# Danfoss302Pi_Interface.net
KiCad netlist of a schematic drawn in Altium Designer
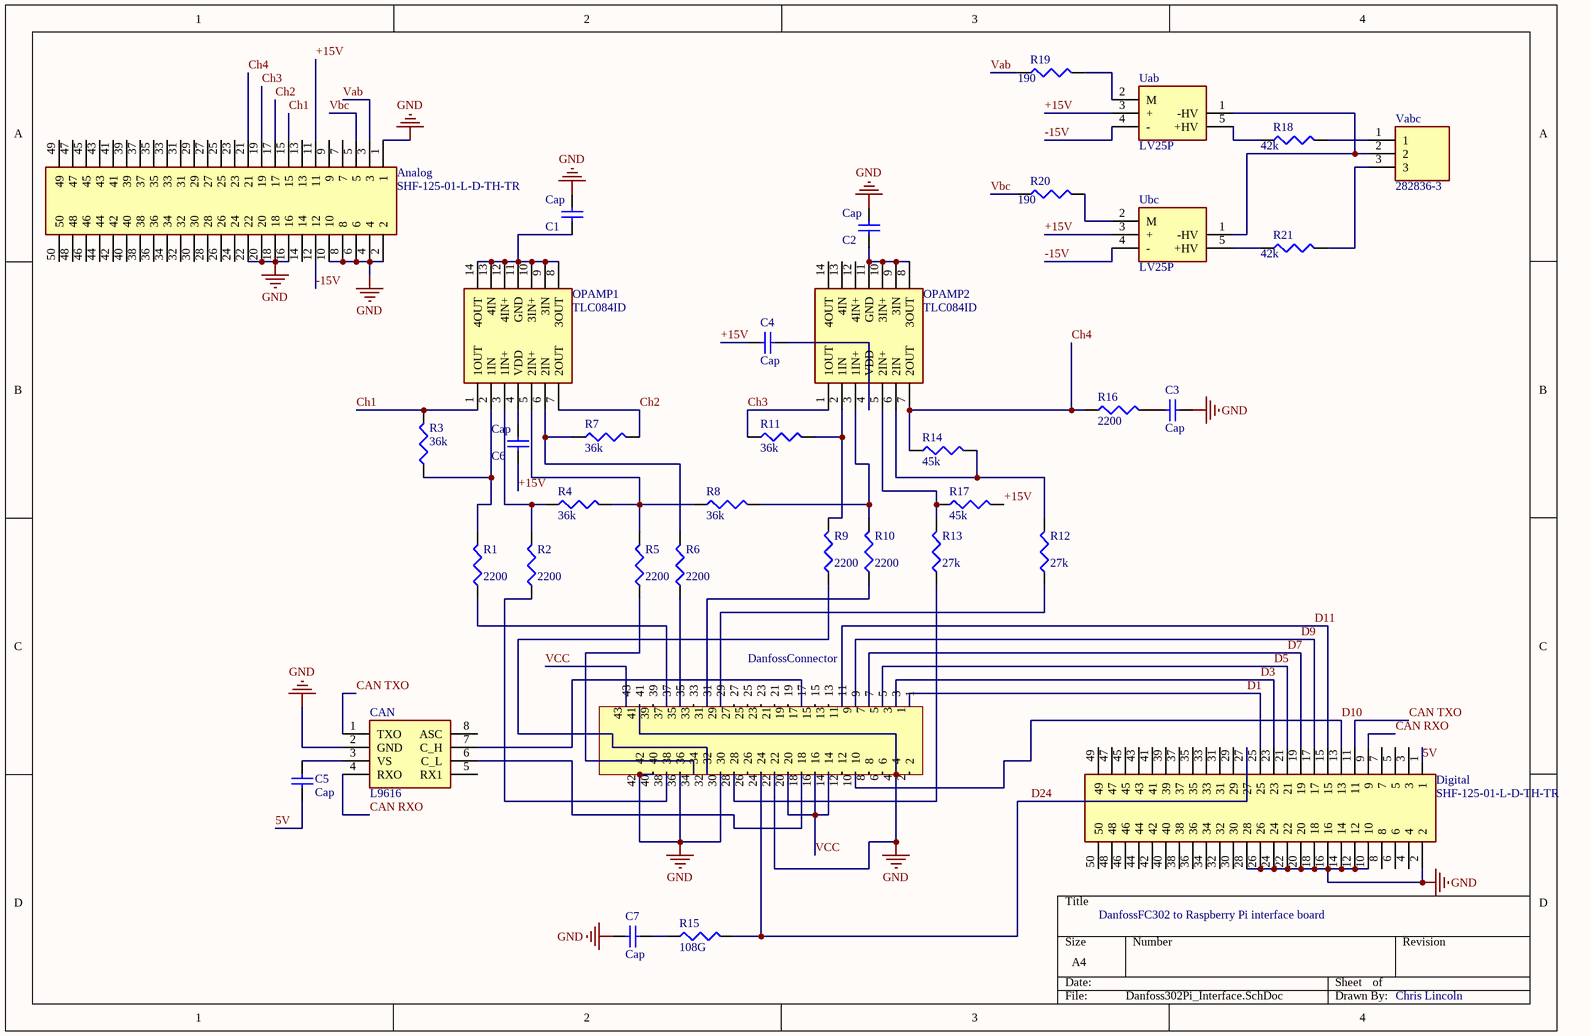
[diagram p0: Danfoss302Pi_Interface.SchDoc]

(export (version "E")
  (design (tool "Eeschema 10.0.6"))
  (components
    (comp (ref "Analog")
      (value "SHF-125-01-L-D-TH-TR")
      (footprint "SamacSys:SHF12501LDTHTR")
      (description "Connector")
      (fields (field (name "MOUSER PART NUMBER") "200-SHF12501LDTHTR"))
      (libsource (lib "*") (part "SHF-125-01-L-D-TH-TR"))
    )
    (comp (ref "C1")
      (value "Cap")
      (footprint "C1206")
      (description "Capacitor (Semiconductor SIM Model)")
      (fields (field (name "PUBLISHER") "Altium Limited"))
      (libsource (lib "Miscellaneous Devices") (part "Cap Semi"))
    )
    (comp (ref "C2")
      (value "Cap")
      (footprint "C1206")
      (description "Capacitor (Semiconductor SIM Model)")
      (fields (field (name "PUBLISHER") "Altium Limited"))
      (libsource (lib "Miscellaneous Devices") (part "Cap Semi"))
    )
    (comp (ref "C3")
      (value "Cap")
      (footprint "C1206")
      (description "Capacitor (Semiconductor SIM Model)")
      (fields (field (name "PUBLISHER") "Altium Limited"))
      (libsource (lib "Miscellaneous Devices") (part "Cap Semi"))
    )
    (comp (ref "C4")
      (value "Cap")
      (footprint "C1206")
      (description "Capacitor (Semiconductor SIM Model)")
      (fields (field (name "PUBLISHER") "Altium Limited"))
      (libsource (lib "Miscellaneous Devices") (part "Cap Semi"))
    )
    (comp (ref "C5")
      (value "Cap")
      (footprint "C1206")
      (description "Capacitor (Semiconductor SIM Model)")
      (fields (field (name "PUBLISHER") "Altium Limited"))
      (libsource (lib "Miscellaneous Devices") (part "Cap Semi"))
    )
    (comp (ref "C6")
      (value "Cap")
      (footprint "C1206")
      (description "Capacitor (Semiconductor SIM Model)")
      (fields (field (name "PUBLISHER") "Altium Limited"))
      (libsource (lib "Miscellaneous Devices") (part "Cap Semi"))
    )
    (comp (ref "C7")
      (value "Cap")
      (footprint "C1206")
      (description "Capacitor (Semiconductor SIM Model)")
      (fields (field (name "PUBLISHER") "Altium Limited"))
      (libsource (lib "Miscellaneous Devices") (part "Cap Semi"))
    )
    (comp (ref "CAN")
      (value "L9616")
      (footprint "SamacSys:SOIC127P600X175-8N")
      (description "Integrated Circuit")
      (fields (field (name "MOUSER PART NUMBER") "511-L9616"))
      (libsource (lib "*") (part "L9616"))
    )
    (comp (ref "DanfossConeector")
      (value "DanfossConnector")
      (footprint "DanfossConnector")
      (libsource (lib "Schlib1") (part "DanfossConnector"))
    )
    (comp (ref "Digital")
      (value "SHF-125-01-L-D-TH-TR")
      (footprint "SamacSys:SHF12501LDTHTR")
      (description "Connector")
      (fields (field (name "MOUSER PART NUMBER") "200-SHF12501LDTHTR"))
      (libsource (lib "*") (part "SHF-125-01-L-D-TH-TR"))
    )
    (comp (ref "OPAMP1")
      (value "TLC084ID")
      (footprint "SamacSys:SOIC127P600X175-14N")
      (description "Integrated Circuit")
      (fields (field (name "MOUSER PART NUMBER") "595-TLC084ID"))
      (libsource (lib "*") (part "TLC084ID"))
    )
    (comp (ref "OPAMP2")
      (value "TLC084ID")
      (footprint "SamacSys:SOIC127P600X175-14N")
      (description "Integrated Circuit")
      (fields (field (name "MOUSER PART NUMBER") "595-TLC084ID"))
      (libsource (lib "*") (part "TLC084ID"))
    )
    (comp (ref "R1")
      (value "2200")
      (footprint "J1-0603")
      (description "Resistor")
      (fields (field (name "Comment") "Res3") (field (name "PUBLISHER") "Altium Limited"))
      (libsource (lib "Miscellaneous Devices") (part "Res3"))
    )
    (comp (ref "R2")
      (value "2200")
      (footprint "J1-0603")
      (description "Resistor")
      (fields (field (name "Comment") "Res3") (field (name "PUBLISHER") "Altium Limited"))
      (libsource (lib "Miscellaneous Devices") (part "Res3"))
    )
    (comp (ref "R3")
      (value "36k")
      (footprint "J1-0603")
      (description "Resistor")
      (fields (field (name "Comment") "Res3") (field (name "PUBLISHER") "Altium Limited"))
      (libsource (lib "Miscellaneous Devices") (part "Res3"))
    )
    (comp (ref "R4")
      (value "36k")
      (footprint "J1-0603")
      (description "Resistor")
      (fields (field (name "Comment") "Res3") (field (name "PUBLISHER") "Altium Limited"))
      (libsource (lib "Miscellaneous Devices") (part "Res3"))
    )
    (comp (ref "R5")
      (value "2200")
      (footprint "J1-0603")
      (description "Resistor")
      (fields (field (name "Comment") "Res3") (field (name "PUBLISHER") "Altium Limited"))
      (libsource (lib "Miscellaneous Devices") (part "Res3"))
    )
    (comp (ref "R6")
      (value "2200")
      (footprint "J1-0603")
      (description "Resistor")
      (fields (field (name "Comment") "Res3") (field (name "PUBLISHER") "Altium Limited"))
      (libsource (lib "Miscellaneous Devices") (part "Res3"))
    )
    (comp (ref "R7")
      (value "36k")
      (footprint "J1-0603")
      (description "Resistor")
      (fields (field (name "Comment") "Res3") (field (name "PUBLISHER") "Altium Limited"))
      (libsource (lib "Miscellaneous Devices") (part "Res3"))
    )
    (comp (ref "R8")
      (value "36k")
      (footprint "J1-0603")
      (description "Resistor")
      (fields (field (name "Comment") "Res3") (field (name "PUBLISHER") "Altium Limited"))
      (libsource (lib "Miscellaneous Devices") (part "Res3"))
    )
    (comp (ref "R9")
      (value "2200")
      (footprint "J1-0603")
      (description "Resistor")
      (fields (field (name "Comment") "Res3") (field (name "PUBLISHER") "Altium Limited"))
      (libsource (lib "Miscellaneous Devices") (part "Res3"))
    )
    (comp (ref "R10")
      (value "2200")
      (footprint "J1-0603")
      (description "Resistor")
      (fields (field (name "Comment") "Res3") (field (name "PUBLISHER") "Altium Limited"))
      (libsource (lib "Miscellaneous Devices") (part "Res3"))
    )
    (comp (ref "R11")
      (value "36k")
      (footprint "J1-0603")
      (description "Resistor")
      (fields (field (name "Comment") "Res3") (field (name "PUBLISHER") "Altium Limited"))
      (libsource (lib "Miscellaneous Devices") (part "Res3"))
    )
    (comp (ref "R12")
      (value "27k")
      (footprint "J1-0603")
      (description "Resistor")
      (fields (field (name "Comment") "Res3") (field (name "PUBLISHER") "Altium Limited"))
      (libsource (lib "Miscellaneous Devices") (part "Res3"))
    )
    (comp (ref "R13")
      (value "27k")
      (footprint "J1-0603")
      (description "Resistor")
      (fields (field (name "Comment") "Res3") (field (name "PUBLISHER") "Altium Limited"))
      (libsource (lib "Miscellaneous Devices") (part "Res3"))
    )
    (comp (ref "R14")
      (value "45k")
      (footprint "J1-0603")
      (description "Resistor")
      (fields (field (name "Comment") "Res3") (field (name "PUBLISHER") "Altium Limited"))
      (libsource (lib "Miscellaneous Devices") (part "Res3"))
    )
    (comp (ref "R15")
      (value "108G")
      (footprint "J1-0603")
      (description "Resistor")
      (fields (field (name "Comment") "Res3") (field (name "PUBLISHER") "Altium Limited"))
      (libsource (lib "Miscellaneous Devices") (part "Res3"))
    )
    (comp (ref "R16")
      (value "2200")
      (footprint "J1-0603")
      (description "Resistor")
      (fields (field (name "Comment") "Res3") (field (name "PUBLISHER") "Altium Limited"))
      (libsource (lib "Miscellaneous Devices") (part "Res3"))
    )
    (comp (ref "R17")
      (value "45k")
      (footprint "J1-0603")
      (description "Resistor")
      (fields (field (name "Comment") "Res3") (field (name "PUBLISHER") "Altium Limited"))
      (libsource (lib "Miscellaneous Devices") (part "Res3"))
    )
    (comp (ref "R18")
      (value "42k")
      (footprint "J1-0603")
      (description "Resistor")
      (fields (field (name "Comment") "Res3") (field (name "PUBLISHER") "Altium Limited"))
      (libsource (lib "Miscellaneous Devices") (part "Res3"))
    )
    (comp (ref "R19")
      (value "190")
      (footprint "J1-0603")
      (description "Resistor")
      (fields (field (name "Comment") "Res3") (field (name "PUBLISHER") "Altium Limited"))
      (libsource (lib "Miscellaneous Devices") (part "Res3"))
    )
    (comp (ref "R20")
      (value "190")
      (footprint "J1-0603")
      (description "Resistor")
      (fields (field (name "Comment") "Res3") (field (name "PUBLISHER") "Altium Limited"))
      (libsource (lib "Miscellaneous Devices") (part "Res3"))
    )
    (comp (ref "R21")
      (value "42k")
      (footprint "J1-0603")
      (description "Resistor")
      (fields (field (name "Comment") "Res3") (field (name "PUBLISHER") "Altium Limited"))
      (libsource (lib "Miscellaneous Devices") (part "Res3"))
    )
    (comp (ref "Uab")
      (value "LV25P")
      (footprint "SamacSys:LV-25-P")
      (description "Undefined or Miscellaneous")
      (libsource (lib "*") (part "LV25P"))
    )
    (comp (ref "Ubc")
      (value "LV25P")
      (footprint "SamacSys:LV-25-P")
      (description "Undefined or Miscellaneous")
      (libsource (lib "*") (part "LV25P"))
    )
    (comp (ref "Vabc")
      (value "282836-3")
      (footprint "SamacSys:2828363")
      (description "Connector")
      (fields (field (name "MOUSER PART NUMBER") "571-2828363"))
      (libsource (lib "*") (part "282836-3"))
    )
  )
  (nets
    (net (code "1") (name "/+15V") (class "Default")
      (node (ref "Analog") (pin "11") (pinfunction "11_11") (pintype "passive"))
      (node (ref "C4") (pin "1") (pinfunction "1_1") (pintype "passive"))
      (node (ref "C6") (pin "1") (pinfunction "1_1") (pintype "passive"))
      (node (ref "R17") (pin "2") (pinfunction "2_2") (pintype "passive"))
      (node (ref "Uab") (pin "3") (pinfunction "+_3") (pintype "passive"))
      (node (ref "Ubc") (pin "3") (pinfunction "+_3") (pintype "passive"))
    )
    (net (code "2") (name "/-15V") (class "Default")
      (node (ref "Analog") (pin "12") (pinfunction "12_12") (pintype "passive"))
      (node (ref "Uab") (pin "4") (pinfunction "-_4") (pintype "passive"))
      (node (ref "Ubc") (pin "4") (pinfunction "-_4") (pintype "passive"))
    )
    (net (code "3") (name "/5V") (class "Default")
      (node (ref "C5") (pin "1") (pinfunction "1_1") (pintype "passive"))
      (node (ref "Digital") (pin "1") (pinfunction "1_1") (pintype "passive"))
    )
    (net (code "5") (name "/CAN RXO") (class "Default")
      (node (ref "CAN") (pin "4") (pinfunction "RXO_4") (pintype "passive"))
      (node (ref "Digital") (pin "9") (pinfunction "9_9") (pintype "passive"))
    )
    (net (code "6") (name "/CAN TXO") (class "Default")
      (node (ref "CAN") (pin "1") (pinfunction "TXO_1") (pintype "passive"))
      (node (ref "Digital") (pin "11") (pinfunction "11_11") (pintype "passive"))
    )
    (net (code "7") (name "/Ch1") (class "Default")
      (node (ref "Analog") (pin "15") (pinfunction "15_15") (pintype "passive"))
      (node (ref "OPAMP1") (pin "1") (pinfunction "1OUT_1") (pintype "passive"))
      (node (ref "R3") (pin "2") (pinfunction "2_2") (pintype "passive"))
    )
    (net (code "8") (name "/Ch2") (class "Default")
      (node (ref "Analog") (pin "17") (pinfunction "17_17") (pintype "passive"))
      (node (ref "OPAMP1") (pin "7") (pinfunction "2OUT_7") (pintype "passive"))
      (node (ref "R7") (pin "2") (pinfunction "2_2") (pintype "passive"))
    )
    (net (code "9") (name "/Ch3") (class "Default")
      (node (ref "Analog") (pin "19") (pinfunction "19_19") (pintype "passive"))
      (node (ref "OPAMP2") (pin "1") (pinfunction "1OUT_1") (pintype "passive"))
      (node (ref "R11") (pin "1") (pinfunction "1_1") (pintype "passive"))
    )
    (net (code "10") (name "/Ch4") (class "Default")
      (node (ref "Analog") (pin "21") (pinfunction "21_21") (pintype "passive"))
      (node (ref "OPAMP2") (pin "7") (pinfunction "2OUT_7") (pintype "passive"))
      (node (ref "R14") (pin "1") (pinfunction "1_1") (pintype "passive"))
      (node (ref "R16") (pin "1") (pinfunction "1_1") (pintype "passive"))
    )
    (net (code "11") (name "/D1") (class "Default")
      (node (ref "DanfossConeector") (pin "1") (pinfunction "1_1") (pintype "passive"))
      (node (ref "Digital") (pin "25") (pinfunction "25_25") (pintype "passive"))
    )
    (net (code "12") (name "/D3") (class "Default")
      (node (ref "DanfossConeector") (pin "3") (pinfunction "3_3") (pintype "passive"))
      (node (ref "Digital") (pin "23") (pinfunction "23_23") (pintype "passive"))
    )
    (net (code "13") (name "/D5") (class "Default")
      (node (ref "DanfossConeector") (pin "5") (pinfunction "5_5") (pintype "passive"))
      (node (ref "Digital") (pin "21") (pinfunction "21_21") (pintype "passive"))
    )
    (net (code "14") (name "/D7") (class "Default")
      (node (ref "DanfossConeector") (pin "7") (pinfunction "7_7") (pintype "passive"))
      (node (ref "Digital") (pin "19") (pinfunction "19_19") (pintype "passive"))
    )
    (net (code "15") (name "/D9") (class "Default")
      (node (ref "DanfossConeector") (pin "9") (pinfunction "9_9") (pintype "passive"))
      (node (ref "Digital") (pin "17") (pinfunction "17_17") (pintype "passive"))
    )
    (net (code "16") (name "/D10") (class "Default")
      (node (ref "DanfossConeector") (pin "10") (pinfunction "10_10") (pintype "passive"))
      (node (ref "Digital") (pin "13") (pinfunction "13_13") (pintype "passive"))
    )
    (net (code "17") (name "/D11") (class "Default")
      (node (ref "DanfossConeector") (pin "11") (pinfunction "11_11") (pintype "passive"))
      (node (ref "Digital") (pin "15") (pinfunction "15_15") (pintype "passive"))
    )
    (net (code "18") (name "/D24") (class "Default")
      (node (ref "DanfossConeector") (pin "24") (pinfunction "24_24") (pintype "passive"))
      (node (ref "Digital") (pin "27") (pinfunction "27_27") (pintype "passive"))
      (node (ref "R15") (pin "2") (pinfunction "2_2") (pintype "passive"))
    )
    (net (code "19") (name "/VCC") (class "Default")
      (node (ref "DanfossConeector") (pin "14") (pinfunction "14_14") (pintype "passive"))
      (node (ref "DanfossConeector") (pin "16") (pinfunction "16_16") (pintype "passive"))
      (node (ref "DanfossConeector") (pin "20") (pinfunction "20_20") (pintype "passive"))
      (node (ref "DanfossConeector") (pin "43") (pinfunction "43_43") (pintype "passive"))
    )
    (net (code "20") (name "/Vab") (class "Default")
      (node (ref "Analog") (pin "3") (pinfunction "3_3") (pintype "passive"))
      (node (ref "R19") (pin "1") (pinfunction "1_1") (pintype "passive"))
    )
    (net (code "21") (name "/Vbc") (class "Default")
      (node (ref "Analog") (pin "5") (pinfunction "5_5") (pintype "passive"))
      (node (ref "R20") (pin "1") (pinfunction "1_1") (pintype "passive"))
    )
    (net (code "22") (name "GND") (class "Default")
      (node (ref "Analog") (pin "1") (pinfunction "1_1") (pintype "passive"))
      (node (ref "Analog") (pin "10") (pinfunction "10_10") (pintype "passive"))
      (node (ref "Analog") (pin "16") (pinfunction "16_16") (pintype "passive"))
      (node (ref "Analog") (pin "18") (pinfunction "18_18") (pintype "passive"))
      (node (ref "Analog") (pin "2") (pinfunction "2_2") (pintype "passive"))
      (node (ref "Analog") (pin "20") (pinfunction "20_20") (pintype "passive"))
      (node (ref "Analog") (pin "22") (pinfunction "22_22") (pintype "passive"))
      (node (ref "Analog") (pin "4") (pinfunction "4_4") (pintype "passive"))
      (node (ref "Analog") (pin "6") (pinfunction "6_6") (pintype "passive"))
      (node (ref "Analog") (pin "8") (pinfunction "8_8") (pintype "passive"))
      (node (ref "C1") (pin "2") (pinfunction "2_2") (pintype "passive"))
      (node (ref "C2") (pin "2") (pinfunction "2_2") (pintype "passive"))
      (node (ref "C3") (pin "2") (pinfunction "2_2") (pintype "passive"))
      (node (ref "C7") (pin "1") (pinfunction "1_1") (pintype "passive"))
      (node (ref "CAN") (pin "2") (pinfunction "GND_2") (pintype "passive"))
      (node (ref "DanfossConeector") (pin "22") (pinfunction "22_22") (pintype "passive"))
      (node (ref "DanfossConeector") (pin "30") (pinfunction "30_30") (pintype "passive"))
      (node (ref "DanfossConeector") (pin "36") (pinfunction "36_36") (pintype "passive"))
      (node (ref "DanfossConeector") (pin "4") (pinfunction "4_4") (pintype "passive"))
      (node (ref "DanfossConeector") (pin "40") (pinfunction "40_40") (pintype "passive"))
      (node (ref "DanfossConeector") (pin "41") (pinfunction "41_41") (pintype "passive"))
      (node (ref "DanfossConeector") (pin "42") (pinfunction "42_42") (pintype "passive"))
      (node (ref "Digital") (pin "10") (pinfunction "10_10") (pintype "passive"))
      (node (ref "Digital") (pin "12") (pinfunction "12_12") (pintype "passive"))
      (node (ref "Digital") (pin "14") (pinfunction "14_14") (pintype "passive"))
      (node (ref "Digital") (pin "16") (pinfunction "16_16") (pintype "passive"))
      (node (ref "Digital") (pin "18") (pinfunction "18_18") (pintype "passive"))
      (node (ref "Digital") (pin "2") (pinfunction "2_2") (pintype "passive"))
      (node (ref "Digital") (pin "20") (pinfunction "20_20") (pintype "passive"))
      (node (ref "Digital") (pin "22") (pinfunction "22_22") (pintype "passive"))
      (node (ref "Digital") (pin "24") (pinfunction "24_24") (pintype "passive"))
      (node (ref "Digital") (pin "26") (pinfunction "26_26") (pintype "passive"))
      (node (ref "Digital") (pin "28") (pinfunction "28_28") (pintype "passive"))
    )
    (net (code "23") (name "Net-(C3-Pad1)") (class "Default")
      (node (ref "C3") (pin "1") (pinfunction "1_1") (pintype "passive"))
      (node (ref "R16") (pin "2") (pinfunction "2_2") (pintype "passive"))
    )
    (net (code "24") (name "Net-(C7-Pad2)") (class "Default")
      (node (ref "C7") (pin "2") (pinfunction "2_2") (pintype "passive"))
      (node (ref "R15") (pin "1") (pinfunction "1_1") (pintype "passive"))
    )
    (net (code "25") (name "Net-(CAN-C_H)") (class "Default")
      (node (ref "CAN") (pin "7") (pinfunction "C_H_7") (pintype "passive"))
      (node (ref "DanfossConeector") (pin "17") (pinfunction "17_17") (pintype "passive"))
    )
    (net (code "26") (name "Net-(CAN-C_L)") (class "Default")
      (node (ref "CAN") (pin "6") (pinfunction "C_L_6") (pintype "passive"))
      (node (ref "DanfossConeector") (pin "18") (pinfunction "18_18") (pintype "passive"))
    )
    (net (code "27") (name "Net-(CAN-VS)") (class "Default")
      (node (ref "C5") (pin "2") (pinfunction "2_2") (pintype "passive"))
      (node (ref "CAN") (pin "3") (pinfunction "VS_3") (pintype "passive"))
    )
    (net (code "28") (name "Net-(DanfossConeector-Pad28)") (class "Default")
      (node (ref "DanfossConeector") (pin "28") (pinfunction "28_28") (pintype "passive"))
      (node (ref "R13") (pin "1") (pinfunction "1_1") (pintype "passive"))
    )
    (net (code "29") (name "Net-(DanfossConeector-Pad29)") (class "Default")
      (node (ref "DanfossConeector") (pin "29") (pinfunction "29_29") (pintype "passive"))
      (node (ref "R12") (pin "1") (pinfunction "1_1") (pintype "passive"))
    )
    (net (code "30") (name "Net-(DanfossConeector-Pad31)") (class "Default")
      (node (ref "DanfossConeector") (pin "31") (pinfunction "31_31") (pintype "passive"))
      (node (ref "R10") (pin "1") (pinfunction "1_1") (pintype "passive"))
    )
    (net (code "31") (name "Net-(DanfossConeector-Pad32)") (class "Default")
      (node (ref "DanfossConeector") (pin "32") (pinfunction "32_32") (pintype "passive"))
      (node (ref "R9") (pin "1") (pinfunction "1_1") (pintype "passive"))
    )
    (net (code "32") (name "Net-(DanfossConeector-Pad34)") (class "Default")
      (node (ref "DanfossConeector") (pin "34") (pinfunction "34_34") (pintype "passive"))
      (node (ref "R5") (pin "1") (pinfunction "1_1") (pintype "passive"))
    )
    (net (code "33") (name "Net-(DanfossConeector-Pad35)") (class "Default")
      (node (ref "DanfossConeector") (pin "35") (pinfunction "35_35") (pintype "passive"))
      (node (ref "R6") (pin "1") (pinfunction "1_1") (pintype "passive"))
    )
    (net (code "34") (name "Net-(DanfossConeector-Pad37)") (class "Default")
      (node (ref "DanfossConeector") (pin "37") (pinfunction "37_37") (pintype "passive"))
      (node (ref "R1") (pin "1") (pinfunction "1_1") (pintype "passive"))
    )
    (net (code "35") (name "Net-(DanfossConeector-Pad38)") (class "Default")
      (node (ref "DanfossConeector") (pin "38") (pinfunction "38_38") (pintype "passive"))
      (node (ref "R2") (pin "1") (pinfunction "1_1") (pintype "passive"))
    )
    (net (code "36") (name "Net-(OPAMP1-1IN)") (class "Default")
      (node (ref "OPAMP1") (pin "2") (pinfunction "1IN_2") (pintype "passive"))
      (node (ref "R1") (pin "2") (pinfunction "2_2") (pintype "passive"))
      (node (ref "R3") (pin "1") (pinfunction "1_1") (pintype "passive"))
    )
    (net (code "37") (name "Net-(OPAMP1-1IN+)") (class "Default")
      (node (ref "OPAMP1") (pin "3") (pinfunction "1IN+_3") (pintype "passive"))
      (node (ref "R2") (pin "2") (pinfunction "2_2") (pintype "passive"))
      (node (ref "R4") (pin "1") (pinfunction "1_1") (pintype "passive"))
    )
    (net (code "38") (name "Net-(OPAMP1-2IN)") (class "Default")
      (node (ref "OPAMP1") (pin "6") (pinfunction "2IN_6") (pintype "passive"))
      (node (ref "R6") (pin "2") (pinfunction "2_2") (pintype "passive"))
      (node (ref "R7") (pin "1") (pinfunction "1_1") (pintype "passive"))
    )
    (net (code "39") (name "Net-(OPAMP1-2IN+)") (class "Default")
      (node (ref "OPAMP1") (pin "5") (pinfunction "2IN+_5") (pintype "passive"))
      (node (ref "R4") (pin "2") (pinfunction "2_2") (pintype "passive"))
      (node (ref "R5") (pin "2") (pinfunction "2_2") (pintype "passive"))
      (node (ref "R8") (pin "1") (pinfunction "1_1") (pintype "passive"))
    )
    (net (code "40") (name "Net-(OPAMP1-3IN)") (class "Default")
      (node (ref "C1") (pin "1") (pinfunction "1_1") (pintype "passive"))
      (node (ref "OPAMP1") (pin "10") (pinfunction "3IN+_10") (pintype "passive"))
      (node (ref "OPAMP1") (pin "11") (pinfunction "GND_11") (pintype "passive"))
      (node (ref "OPAMP1") (pin "12") (pinfunction "4IN+_12") (pintype "passive"))
      (node (ref "OPAMP1") (pin "13") (pinfunction "4IN_13") (pintype "passive"))
      (node (ref "OPAMP1") (pin "14") (pinfunction "4OUT_14") (pintype "passive"))
      (node (ref "OPAMP1") (pin "8") (pinfunction "3OUT_8") (pintype "passive"))
      (node (ref "OPAMP1") (pin "9") (pinfunction "3IN_9") (pintype "passive"))
    )
    (net (code "41") (name "Net-(OPAMP1-VDD)") (class "Default")
      (node (ref "C6") (pin "2") (pinfunction "2_2") (pintype "passive"))
      (node (ref "OPAMP1") (pin "4") (pinfunction "VDD_4") (pintype "passive"))
    )
    (net (code "42") (name "Net-(OPAMP2-1IN)") (class "Default")
      (node (ref "OPAMP2") (pin "2") (pinfunction "1IN_2") (pintype "passive"))
      (node (ref "R11") (pin "2") (pinfunction "2_2") (pintype "passive"))
      (node (ref "R9") (pin "2") (pinfunction "2_2") (pintype "passive"))
    )
    (net (code "43") (name "Net-(OPAMP2-1IN+)") (class "Default")
      (node (ref "OPAMP2") (pin "3") (pinfunction "1IN+_3") (pintype "passive"))
      (node (ref "R10") (pin "2") (pinfunction "2_2") (pintype "passive"))
      (node (ref "R8") (pin "2") (pinfunction "2_2") (pintype "passive"))
    )
    (net (code "44") (name "Net-(OPAMP2-2IN)") (class "Default")
      (node (ref "OPAMP2") (pin "6") (pinfunction "2IN_6") (pintype "passive"))
      (node (ref "R12") (pin "2") (pinfunction "2_2") (pintype "passive"))
      (node (ref "R14") (pin "2") (pinfunction "2_2") (pintype "passive"))
    )
    (net (code "45") (name "Net-(OPAMP2-2IN+)") (class "Default")
      (node (ref "OPAMP2") (pin "5") (pinfunction "2IN+_5") (pintype "passive"))
      (node (ref "R13") (pin "2") (pinfunction "2_2") (pintype "passive"))
      (node (ref "R17") (pin "1") (pinfunction "1_1") (pintype "passive"))
    )
    (net (code "46") (name "Net-(OPAMP2-3IN)") (class "Default")
      (node (ref "C2") (pin "1") (pinfunction "1_1") (pintype "passive"))
      (node (ref "OPAMP2") (pin "10") (pinfunction "3IN+_10") (pintype "passive"))
      (node (ref "OPAMP2") (pin "11") (pinfunction "GND_11") (pintype "passive"))
      (node (ref "OPAMP2") (pin "8") (pinfunction "3OUT_8") (pintype "passive"))
      (node (ref "OPAMP2") (pin "9") (pinfunction "3IN_9") (pintype "passive"))
    )
    (net (code "47") (name "Net-(OPAMP2-VDD)") (class "Default")
      (node (ref "C4") (pin "2") (pinfunction "2_2") (pintype "passive"))
      (node (ref "OPAMP2") (pin "4") (pinfunction "VDD_4") (pintype "passive"))
    )
    (net (code "48") (name "Net-(R18-Pad2)") (class "Default")
      (node (ref "R18") (pin "2") (pinfunction "2_2") (pintype "passive"))
      (node (ref "Vabc") (pin "1") (pinfunction "1_1") (pintype "passive"))
    )
    (net (code "49") (name "Net-(R21-Pad2)") (class "Default")
      (node (ref "R21") (pin "2") (pinfunction "2_2") (pintype "passive"))
      (node (ref "Vabc") (pin "3") (pinfunction "3_3") (pintype "passive"))
    )
    (net (code "50") (name "Net-(Uab-+HV)") (class "Default")
      (node (ref "R18") (pin "1") (pinfunction "1_1") (pintype "passive"))
      (node (ref "Uab") (pin "5") (pinfunction "+HV_5") (pintype "passive"))
    )
    (net (code "51") (name "Net-(Uab--HV)") (class "Default")
      (node (ref "Uab") (pin "1") (pinfunction "-HV_1") (pintype "passive"))
      (node (ref "Ubc") (pin "1") (pinfunction "-HV_1") (pintype "passive"))
      (node (ref "Vabc") (pin "2") (pinfunction "2_2") (pintype "passive"))
    )
    (net (code "52") (name "Net-(Uab-M)") (class "Default")
      (node (ref "R19") (pin "2") (pinfunction "2_2") (pintype "passive"))
      (node (ref "Uab") (pin "2") (pinfunction "M_2") (pintype "passive"))
    )
    (net (code "53") (name "Net-(Ubc-+HV)") (class "Default")
      (node (ref "R21") (pin "1") (pinfunction "1_1") (pintype "passive"))
      (node (ref "Ubc") (pin "5") (pinfunction "+HV_5") (pintype "passive"))
    )
    (net (code "54") (name "Net-(Ubc-M)") (class "Default")
      (node (ref "R20") (pin "2") (pinfunction "2_2") (pintype "passive"))
      (node (ref "Ubc") (pin "2") (pinfunction "M_2") (pintype "passive"))
    )
    (net (code "55") (name "unconnected-(Analog-Pad7)") (class "Default")
      (node (ref "Analog") (pin "7") (pinfunction "7_7") (pintype "passive"))
    )
    (net (code "56") (name "unconnected-(Analog-Pad9)") (class "Default")
      (node (ref "Analog") (pin "9") (pinfunction "9_9") (pintype "passive"))
    )
    (net (code "57") (name "unconnected-(Analog-Pad13)") (class "Default")
      (node (ref "Analog") (pin "13") (pinfunction "13_13") (pintype "passive"))
    )
    (net (code "58") (name "unconnected-(Analog-Pad14)") (class "Default")
      (node (ref "Analog") (pin "14") (pinfunction "14_14") (pintype "passive"))
    )
    (net (code "59") (name "unconnected-(Analog-Pad23)") (class "Default")
      (node (ref "Analog") (pin "23") (pinfunction "23_23") (pintype "passive"))
    )
    (net (code "60") (name "unconnected-(Analog-Pad24)") (class "Default")
      (node (ref "Analog") (pin "24") (pinfunction "24_24") (pintype "passive"))
    )
    (net (code "61") (name "unconnected-(Analog-Pad25)") (class "Default")
      (node (ref "Analog") (pin "25") (pinfunction "25_25") (pintype "passive"))
    )
    (net (code "62") (name "unconnected-(Analog-Pad26)") (class "Default")
      (node (ref "Analog") (pin "26") (pinfunction "26_26") (pintype "passive"))
    )
    (net (code "63") (name "unconnected-(Analog-Pad27)") (class "Default")
      (node (ref "Analog") (pin "27") (pinfunction "27_27") (pintype "passive"))
    )
    (net (code "64") (name "unconnected-(Analog-Pad28)") (class "Default")
      (node (ref "Analog") (pin "28") (pinfunction "28_28") (pintype "passive"))
    )
    (net (code "65") (name "unconnected-(Analog-Pad29)") (class "Default")
      (node (ref "Analog") (pin "29") (pinfunction "29_29") (pintype "passive"))
    )
    (net (code "66") (name "unconnected-(Analog-Pad30)") (class "Default")
      (node (ref "Analog") (pin "30") (pinfunction "30_30") (pintype "passive"))
    )
    (net (code "67") (name "unconnected-(Analog-Pad31)") (class "Default")
      (node (ref "Analog") (pin "31") (pinfunction "31_31") (pintype "passive"))
    )
    (net (code "68") (name "unconnected-(Analog-Pad32)") (class "Default")
      (node (ref "Analog") (pin "32") (pinfunction "32_32") (pintype "passive"))
    )
    (net (code "69") (name "unconnected-(Analog-Pad33)") (class "Default")
      (node (ref "Analog") (pin "33") (pinfunction "33_33") (pintype "passive"))
    )
    (net (code "70") (name "unconnected-(Analog-Pad34)") (class "Default")
      (node (ref "Analog") (pin "34") (pinfunction "34_34") (pintype "passive"))
    )
    (net (code "71") (name "unconnected-(Analog-Pad35)") (class "Default")
      (node (ref "Analog") (pin "35") (pinfunction "35_35") (pintype "passive"))
    )
    (net (code "72") (name "unconnected-(Analog-Pad36)") (class "Default")
      (node (ref "Analog") (pin "36") (pinfunction "36_36") (pintype "passive"))
    )
    (net (code "73") (name "unconnected-(Analog-Pad37)") (class "Default")
      (node (ref "Analog") (pin "37") (pinfunction "37_37") (pintype "passive"))
    )
    (net (code "74") (name "unconnected-(Analog-Pad38)") (class "Default")
      (node (ref "Analog") (pin "38") (pinfunction "38_38") (pintype "passive"))
    )
    (net (code "75") (name "unconnected-(Analog-Pad39)") (class "Default")
      (node (ref "Analog") (pin "39") (pinfunction "39_39") (pintype "passive"))
    )
    (net (code "76") (name "unconnected-(Analog-Pad40)") (class "Default")
      (node (ref "Analog") (pin "40") (pinfunction "40_40") (pintype "passive"))
    )
    (net (code "77") (name "unconnected-(Analog-Pad41)") (class "Default")
      (node (ref "Analog") (pin "41") (pinfunction "41_41") (pintype "passive"))
    )
    (net (code "78") (name "unconnected-(Analog-Pad42)") (class "Default")
      (node (ref "Analog") (pin "42") (pinfunction "42_42") (pintype "passive"))
    )
    (net (code "79") (name "unconnected-(Analog-Pad43)") (class "Default")
      (node (ref "Analog") (pin "43") (pinfunction "43_43") (pintype "passive"))
    )
    (net (code "80") (name "unconnected-(Analog-Pad44)") (class "Default")
      (node (ref "Analog") (pin "44") (pinfunction "44_44") (pintype "passive"))
    )
    (net (code "81") (name "unconnected-(Analog-Pad45)") (class "Default")
      (node (ref "Analog") (pin "45") (pinfunction "45_45") (pintype "passive"))
    )
    (net (code "82") (name "unconnected-(Analog-Pad46)") (class "Default")
      (node (ref "Analog") (pin "46") (pinfunction "46_46") (pintype "passive"))
    )
    (net (code "83") (name "unconnected-(Analog-Pad47)") (class "Default")
      (node (ref "Analog") (pin "47") (pinfunction "47_47") (pintype "passive"))
    )
    (net (code "84") (name "unconnected-(Analog-Pad48)") (class "Default")
      (node (ref "Analog") (pin "48") (pinfunction "48_48") (pintype "passive"))
    )
    (net (code "85") (name "unconnected-(Analog-Pad49)") (class "Default")
      (node (ref "Analog") (pin "49") (pinfunction "49_49") (pintype "passive"))
    )
    (net (code "86") (name "unconnected-(Analog-Pad50)") (class "Default")
      (node (ref "Analog") (pin "50") (pinfunction "50_50") (pintype "passive"))
    )
    (net (code "87") (name "unconnected-(CAN-ASC-Pad8)") (class "Default")
      (node (ref "CAN") (pin "8") (pinfunction "ASC_8") (pintype "passive"))
    )
    (net (code "88") (name "unconnected-(CAN-RX1-Pad5)") (class "Default")
      (node (ref "CAN") (pin "5") (pinfunction "RX1_5") (pintype "passive"))
    )
    (net (code "89") (name "unconnected-(DanfossConeector-Pad2)") (class "Default")
      (node (ref "DanfossConeector") (pin "2") (pinfunction "2_2") (pintype "passive"))
    )
    (net (code "90") (name "unconnected-(DanfossConeector-Pad6)") (class "Default")
      (node (ref "DanfossConeector") (pin "6") (pinfunction "6_6") (pintype "passive"))
    )
    (net (code "91") (name "unconnected-(DanfossConeector-Pad8)") (class "Default")
      (node (ref "DanfossConeector") (pin "8") (pinfunction "8_8") (pintype "passive"))
    )
    (net (code "92") (name "unconnected-(DanfossConeector-Pad12)") (class "Default")
      (node (ref "DanfossConeector") (pin "12") (pinfunction "12_12") (pintype "passive"))
    )
    (net (code "93") (name "unconnected-(DanfossConeector-Pad13)") (class "Default")
      (node (ref "DanfossConeector") (pin "13") (pinfunction "13_13") (pintype "passive"))
    )
    (net (code "94") (name "unconnected-(DanfossConeector-Pad15)") (class "Default")
      (node (ref "DanfossConeector") (pin "15") (pinfunction "15_15") (pintype "passive"))
    )
    (net (code "95") (name "unconnected-(DanfossConeector-Pad19)") (class "Default")
      (node (ref "DanfossConeector") (pin "19") (pinfunction "19_19") (pintype "passive"))
    )
    (net (code "96") (name "unconnected-(DanfossConeector-Pad21)") (class "Default")
      (node (ref "DanfossConeector") (pin "21") (pinfunction "21_21") (pintype "passive"))
    )
    (net (code "97") (name "unconnected-(DanfossConeector-Pad23)") (class "Default")
      (node (ref "DanfossConeector") (pin "23") (pinfunction "23_23") (pintype "passive"))
    )
    (net (code "98") (name "unconnected-(DanfossConeector-Pad25)") (class "Default")
      (node (ref "DanfossConeector") (pin "25") (pinfunction "25_25") (pintype "passive"))
    )
    (net (code "99") (name "unconnected-(DanfossConeector-Pad26)") (class "Default")
      (node (ref "DanfossConeector") (pin "26") (pinfunction "26_26") (pintype "passive"))
    )
    (net (code "100") (name "unconnected-(DanfossConeector-Pad27)") (class "Default")
      (node (ref "DanfossConeector") (pin "27") (pinfunction "27_27") (pintype "passive"))
    )
    (net (code "101") (name "unconnected-(DanfossConeector-Pad33)") (class "Default")
      (node (ref "DanfossConeector") (pin "33") (pinfunction "33_33") (pintype "passive"))
    )
    (net (code "102") (name "unconnected-(DanfossConeector-Pad39)") (class "Default")
      (node (ref "DanfossConeector") (pin "39") (pinfunction "39_39") (pintype "passive"))
    )
    (net (code "103") (name "unconnected-(Digital-Pad3)") (class "Default")
      (node (ref "Digital") (pin "3") (pinfunction "3_3") (pintype "passive"))
    )
    (net (code "104") (name "unconnected-(Digital-Pad4)") (class "Default")
      (node (ref "Digital") (pin "4") (pinfunction "4_4") (pintype "passive"))
    )
    (net (code "105") (name "unconnected-(Digital-Pad5)") (class "Default")
      (node (ref "Digital") (pin "5") (pinfunction "5_5") (pintype "passive"))
    )
    (net (code "106") (name "unconnected-(Digital-Pad6)") (class "Default")
      (node (ref "Digital") (pin "6") (pinfunction "6_6") (pintype "passive"))
    )
    (net (code "107") (name "unconnected-(Digital-Pad7)") (class "Default")
      (node (ref "Digital") (pin "7") (pinfunction "7_7") (pintype "passive"))
    )
    (net (code "108") (name "unconnected-(Digital-Pad8)") (class "Default")
      (node (ref "Digital") (pin "8") (pinfunction "8_8") (pintype "passive"))
    )
    (net (code "109") (name "unconnected-(Digital-Pad29)") (class "Default")
      (node (ref "Digital") (pin "29") (pinfunction "29_29") (pintype "passive"))
    )
    (net (code "110") (name "unconnected-(Digital-Pad30)") (class "Default")
      (node (ref "Digital") (pin "30") (pinfunction "30_30") (pintype "passive"))
    )
    (net (code "111") (name "unconnected-(Digital-Pad31)") (class "Default")
      (node (ref "Digital") (pin "31") (pinfunction "31_31") (pintype "passive"))
    )
    (net (code "112") (name "unconnected-(Digital-Pad32)") (class "Default")
      (node (ref "Digital") (pin "32") (pinfunction "32_32") (pintype "passive"))
    )
    (net (code "113") (name "unconnected-(Digital-Pad33)") (class "Default")
      (node (ref "Digital") (pin "33") (pinfunction "33_33") (pintype "passive"))
    )
    (net (code "114") (name "unconnected-(Digital-Pad34)") (class "Default")
      (node (ref "Digital") (pin "34") (pinfunction "34_34") (pintype "passive"))
    )
    (net (code "115") (name "unconnected-(Digital-Pad35)") (class "Default")
      (node (ref "Digital") (pin "35") (pinfunction "35_35") (pintype "passive"))
    )
    (net (code "116") (name "unconnected-(Digital-Pad36)") (class "Default")
      (node (ref "Digital") (pin "36") (pinfunction "36_36") (pintype "passive"))
    )
    (net (code "117") (name "unconnected-(Digital-Pad37)") (class "Default")
      (node (ref "Digital") (pin "37") (pinfunction "37_37") (pintype "passive"))
    )
    (net (code "118") (name "unconnected-(Digital-Pad38)") (class "Default")
      (node (ref "Digital") (pin "38") (pinfunction "38_38") (pintype "passive"))
    )
    (net (code "119") (name "unconnected-(Digital-Pad39)") (class "Default")
      (node (ref "Digital") (pin "39") (pinfunction "39_39") (pintype "passive"))
    )
    (net (code "120") (name "unconnected-(Digital-Pad40)") (class "Default")
      (node (ref "Digital") (pin "40") (pinfunction "40_40") (pintype "passive"))
    )
    (net (code "121") (name "unconnected-(Digital-Pad41)") (class "Default")
      (node (ref "Digital") (pin "41") (pinfunction "41_41") (pintype "passive"))
    )
    (net (code "122") (name "unconnected-(Digital-Pad42)") (class "Default")
      (node (ref "Digital") (pin "42") (pinfunction "42_42") (pintype "passive"))
    )
    (net (code "123") (name "unconnected-(Digital-Pad43)") (class "Default")
      (node (ref "Digital") (pin "43") (pinfunction "43_43") (pintype "passive"))
    )
    (net (code "124") (name "unconnected-(Digital-Pad44)") (class "Default")
      (node (ref "Digital") (pin "44") (pinfunction "44_44") (pintype "passive"))
    )
    (net (code "125") (name "unconnected-(Digital-Pad45)") (class "Default")
      (node (ref "Digital") (pin "45") (pinfunction "45_45") (pintype "passive"))
    )
    (net (code "126") (name "unconnected-(Digital-Pad46)") (class "Default")
      (node (ref "Digital") (pin "46") (pinfunction "46_46") (pintype "passive"))
    )
    (net (code "127") (name "unconnected-(Digital-Pad47)") (class "Default")
      (node (ref "Digital") (pin "47") (pinfunction "47_47") (pintype "passive"))
    )
    (net (code "128") (name "unconnected-(Digital-Pad48)") (class "Default")
      (node (ref "Digital") (pin "48") (pinfunction "48_48") (pintype "passive"))
    )
    (net (code "129") (name "unconnected-(Digital-Pad49)") (class "Default")
      (node (ref "Digital") (pin "49") (pinfunction "49_49") (pintype "passive"))
    )
    (net (code "130") (name "unconnected-(Digital-Pad50)") (class "Default")
      (node (ref "Digital") (pin "50") (pinfunction "50_50") (pintype "passive"))
    )
    (net (code "131") (name "unconnected-(OPAMP2-4IN+-Pad12)") (class "Default")
      (node (ref "OPAMP2") (pin "12") (pinfunction "4IN+_12") (pintype "passive"))
    )
    (net (code "132") (name "unconnected-(OPAMP2-4IN-Pad13)") (class "Default")
      (node (ref "OPAMP2") (pin "13") (pinfunction "4IN_13") (pintype "passive"))
    )
    (net (code "133") (name "unconnected-(OPAMP2-4OUT-Pad14)") (class "Default")
      (node (ref "OPAMP2") (pin "14") (pinfunction "4OUT_14") (pintype "passive"))
    )
  )
)
